# jacarerele.net
KiCad netlist of a schematic drawn in EAGLE
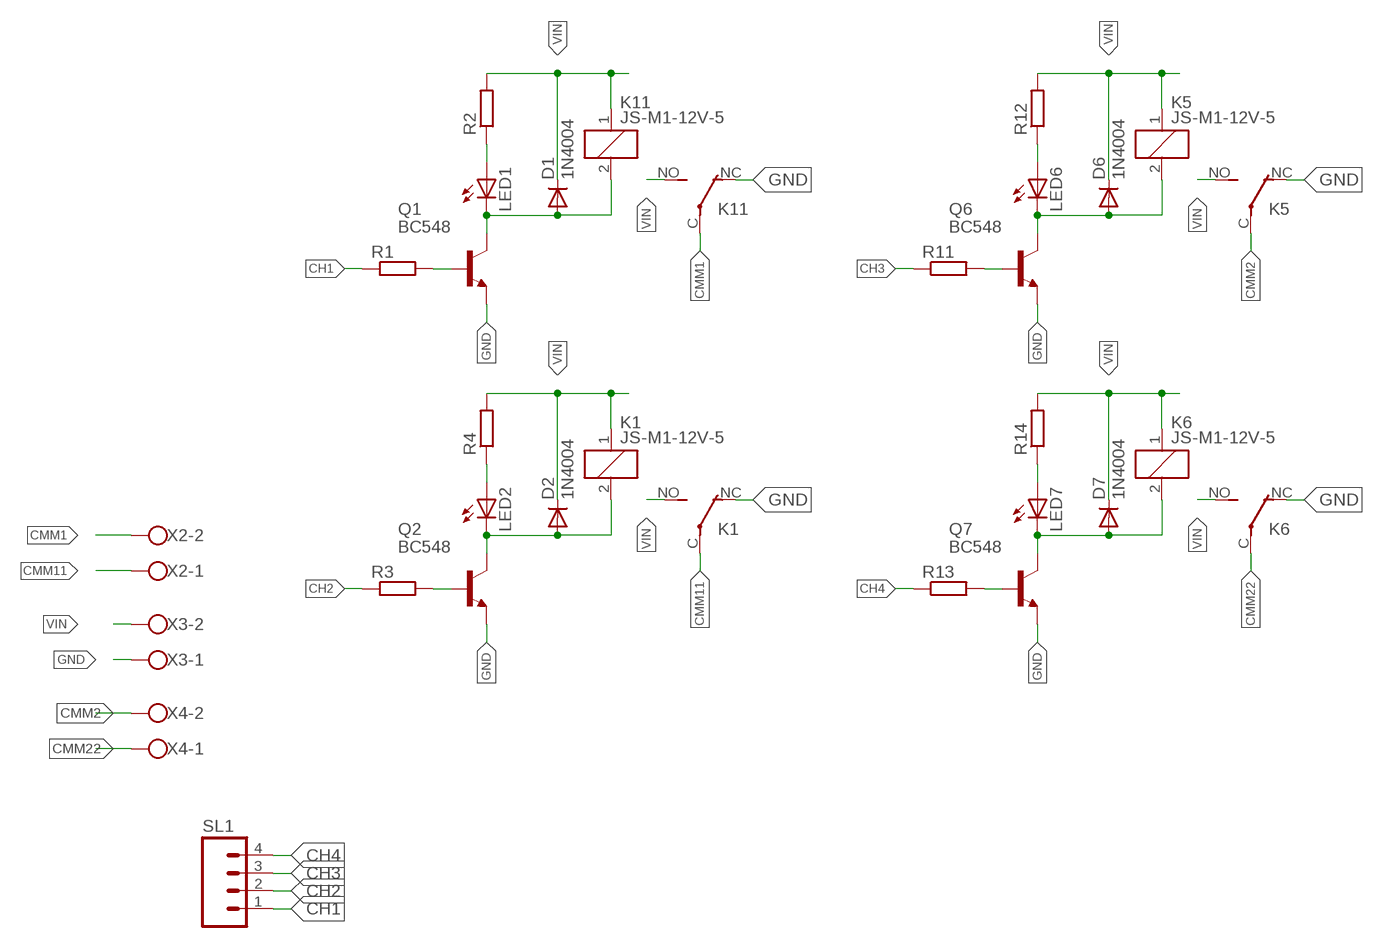
[diagram p0: schematic, sheet 1]

(export (version "E")
  (design (tool "Eeschema 10.0.6"))
  (components
    (comp (ref "D1")
      (value "1N4004")
      (footprint "eagle-import:DO41-10")
      (libsource (lib "eagle-import") (part "1N4004"))
    )
    (comp (ref "D2")
      (value "1N4004")
      (footprint "eagle-import:DO41-10")
      (libsource (lib "eagle-import") (part "1N4004"))
    )
    (comp (ref "D6")
      (value "1N4004")
      (footprint "eagle-import:DO41-10")
      (libsource (lib "eagle-import") (part "1N4004"))
    )
    (comp (ref "D7")
      (value "1N4004")
      (footprint "eagle-import:DO41-10")
      (libsource (lib "eagle-import") (part "1N4004"))
    )
    (comp (ref "K1")
      (value "JS-M1-12V-5")
      (footprint "eagle-import:JS-M")
      (fields (field (name "MF") "FARNELL") (field (name "MPN") "JSM1-12V-5"))
      (libsource (lib "eagle-import") (part "JS-M1-12V-5"))
    )
    (comp (ref "K5")
      (value "JS-M1-12V-5")
      (footprint "eagle-import:JS-M")
      (fields (field (name "MF") "FARNELL") (field (name "MPN") "JSM1-12V-5"))
      (libsource (lib "eagle-import") (part "JS-M1-12V-5"))
    )
    (comp (ref "K6")
      (value "JS-M1-12V-5")
      (footprint "eagle-import:JS-M")
      (fields (field (name "MF") "FARNELL") (field (name "MPN") "JSM1-12V-5"))
      (libsource (lib "eagle-import") (part "JS-M1-12V-5"))
    )
    (comp (ref "K11")
      (value "JS-M1-12V-5")
      (footprint "eagle-import:JS-M")
      (fields (field (name "MF") "FARNELL") (field (name "MPN") "JSM1-12V-5"))
      (libsource (lib "eagle-import") (part "JS-M1-12V-5"))
    )
    (comp (ref "LED1")
      (value "LED5MM")
      (footprint "eagle-import:LED5MM")
      (libsource (lib "eagle-import") (part "LED5MM"))
    )
    (comp (ref "LED2")
      (value "LED5MM")
      (footprint "eagle-import:LED5MM")
      (libsource (lib "eagle-import") (part "LED5MM"))
    )
    (comp (ref "LED6")
      (value "LED5MM")
      (footprint "eagle-import:LED5MM")
      (libsource (lib "eagle-import") (part "LED5MM"))
    )
    (comp (ref "LED7")
      (value "LED5MM")
      (footprint "eagle-import:LED5MM")
      (libsource (lib "eagle-import") (part "LED5MM"))
    )
    (comp (ref "Q1")
      (value "BC548")
      (footprint "eagle-import:TO92-EBC")
      (libsource (lib "eagle-import") (part "BC548"))
    )
    (comp (ref "Q2")
      (value "BC548")
      (footprint "eagle-import:TO92-EBC")
      (libsource (lib "eagle-import") (part "BC548"))
    )
    (comp (ref "Q6")
      (value "BC548")
      (footprint "eagle-import:TO92-EBC")
      (libsource (lib "eagle-import") (part "BC548"))
    )
    (comp (ref "Q7")
      (value "BC548")
      (footprint "eagle-import:TO92-EBC")
      (libsource (lib "eagle-import") (part "BC548"))
    )
    (comp (ref "R1")
      (value "R-EU_0207/10")
      (footprint "eagle-import:0207_10")
      (libsource (lib "eagle-import") (part "R-EU_0207/10"))
    )
    (comp (ref "R2")
      (value "R-EU_0207/10")
      (footprint "eagle-import:0207_10")
      (libsource (lib "eagle-import") (part "R-EU_0207/10"))
    )
    (comp (ref "R3")
      (value "R-EU_0207/10")
      (footprint "eagle-import:0207_10")
      (libsource (lib "eagle-import") (part "R-EU_0207/10"))
    )
    (comp (ref "R4")
      (value "R-EU_0207/10")
      (footprint "eagle-import:0207_10")
      (libsource (lib "eagle-import") (part "R-EU_0207/10"))
    )
    (comp (ref "R11")
      (value "R-EU_0207/10")
      (footprint "eagle-import:0207_10")
      (libsource (lib "eagle-import") (part "R-EU_0207/10"))
    )
    (comp (ref "R12")
      (value "R-EU_0207/10")
      (footprint "eagle-import:0207_10")
      (libsource (lib "eagle-import") (part "R-EU_0207/10"))
    )
    (comp (ref "R13")
      (value "R-EU_0207/10")
      (footprint "eagle-import:0207_10")
      (libsource (lib "eagle-import") (part "R-EU_0207/10"))
    )
    (comp (ref "R14")
      (value "R-EU_0207/10")
      (footprint "eagle-import:0207_10")
      (libsource (lib "eagle-import") (part "R-EU_0207/10"))
    )
    (comp (ref "SL1")
      (value "MA04")
      (footprint "eagle-import:04PA")
      (libsource (lib "eagle-import") (part "MA04"))
    )
    (comp (ref "X2")
      (value "W237-102")
      (footprint "eagle-import:W237-102")
      (fields (field (name "MPN") "237-102"))
      (libsource (lib "eagle-import") (part "W237-102"))
    )
    (comp (ref "X3")
      (value "W237-102")
      (footprint "eagle-import:W237-102")
      (fields (field (name "MPN") "237-102"))
      (libsource (lib "eagle-import") (part "W237-102"))
    )
    (comp (ref "X4")
      (value "W237-102")
      (footprint "eagle-import:W237-102")
      (fields (field (name "MPN") "237-102"))
      (libsource (lib "eagle-import") (part "W237-102"))
    )
  )
  (nets
    (net (code "1") (name "CH1") (class "Default")
      (node (ref "R1") (pin "1") (pinfunction "1_1") (pintype "passive"))
      (node (ref "SL1") (pin "1") (pinfunction "1_1") (pintype "passive"))
    )
    (net (code "2") (name "CH2") (class "Default")
      (node (ref "R3") (pin "1") (pinfunction "1_1") (pintype "passive"))
      (node (ref "SL1") (pin "2") (pinfunction "2_2") (pintype "passive"))
    )
    (net (code "3") (name "CH3") (class "Default")
      (node (ref "R11") (pin "1") (pinfunction "1_1") (pintype "passive"))
      (node (ref "SL1") (pin "3") (pinfunction "3_3") (pintype "passive"))
    )
    (net (code "4") (name "CH4") (class "Default")
      (node (ref "R13") (pin "1") (pinfunction "1_1") (pintype "passive"))
      (node (ref "SL1") (pin "4") (pinfunction "4_4") (pintype "passive"))
    )
    (net (code "5") (name "CMM1") (class "Default")
      (node (ref "K11") (pin "C") (pinfunction "P_C") (pintype "passive"))
      (node (ref "X2") (pin "2") (pinfunction "KL_2") (pintype "passive"))
    )
    (net (code "6") (name "CMM2") (class "Default")
      (node (ref "K5") (pin "C") (pinfunction "P_C") (pintype "passive"))
      (node (ref "X4") (pin "2") (pinfunction "KL_2") (pintype "passive"))
    )
    (net (code "7") (name "CMM11") (class "Default")
      (node (ref "K1") (pin "C") (pinfunction "P_C") (pintype "passive"))
      (node (ref "X2") (pin "1") (pinfunction "KL_1") (pintype "passive"))
    )
    (net (code "8") (name "CMM22") (class "Default")
      (node (ref "K6") (pin "C") (pinfunction "P_C") (pintype "passive"))
      (node (ref "X4") (pin "1") (pinfunction "KL_1") (pintype "passive"))
    )
    (net (code "9") (name "GND") (class "Default")
      (node (ref "K1") (pin "NC") (pinfunction "O_NC") (pintype "passive"))
      (node (ref "K11") (pin "NC") (pinfunction "O_NC") (pintype "passive"))
      (node (ref "K5") (pin "NC") (pinfunction "O_NC") (pintype "passive"))
      (node (ref "K6") (pin "NC") (pinfunction "O_NC") (pintype "passive"))
      (node (ref "Q1") (pin "E") (pinfunction "E_E") (pintype "passive"))
      (node (ref "Q2") (pin "E") (pinfunction "E_E") (pintype "passive"))
      (node (ref "Q6") (pin "E") (pinfunction "E_E") (pintype "passive"))
      (node (ref "Q7") (pin "E") (pinfunction "E_E") (pintype "passive"))
      (node (ref "X3") (pin "1") (pinfunction "KL_1") (pintype "passive"))
    )
    (net (code "10") (name "Net-(LED1-C)") (class "Default")
      (node (ref "D1") (pin "A") (pinfunction "A_A") (pintype "passive"))
      (node (ref "K11") (pin "2") (pinfunction "2_2") (pintype "passive"))
      (node (ref "LED1") (pin "K") (pinfunction "C_K") (pintype "passive"))
      (node (ref "Q1") (pin "C") (pinfunction "C_C") (pintype "passive"))
    )
    (net (code "11") (name "Net-(LED1-PadA)") (class "Default")
      (node (ref "LED1") (pin "A") (pinfunction "A_A") (pintype "passive"))
      (node (ref "R2") (pin "1") (pinfunction "1_1") (pintype "passive"))
    )
    (net (code "12") (name "Net-(LED2-C)") (class "Default")
      (node (ref "D2") (pin "A") (pinfunction "A_A") (pintype "passive"))
      (node (ref "K1") (pin "2") (pinfunction "2_2") (pintype "passive"))
      (node (ref "LED2") (pin "K") (pinfunction "C_K") (pintype "passive"))
      (node (ref "Q2") (pin "C") (pinfunction "C_C") (pintype "passive"))
    )
    (net (code "13") (name "Net-(LED2-PadA)") (class "Default")
      (node (ref "LED2") (pin "A") (pinfunction "A_A") (pintype "passive"))
      (node (ref "R4") (pin "1") (pinfunction "1_1") (pintype "passive"))
    )
    (net (code "14") (name "Net-(LED6-C)") (class "Default")
      (node (ref "D6") (pin "A") (pinfunction "A_A") (pintype "passive"))
      (node (ref "K5") (pin "2") (pinfunction "2_2") (pintype "passive"))
      (node (ref "LED6") (pin "K") (pinfunction "C_K") (pintype "passive"))
      (node (ref "Q6") (pin "C") (pinfunction "C_C") (pintype "passive"))
    )
    (net (code "15") (name "Net-(LED6-PadA)") (class "Default")
      (node (ref "LED6") (pin "A") (pinfunction "A_A") (pintype "passive"))
      (node (ref "R12") (pin "1") (pinfunction "1_1") (pintype "passive"))
    )
    (net (code "16") (name "Net-(LED7-C)") (class "Default")
      (node (ref "D7") (pin "A") (pinfunction "A_A") (pintype "passive"))
      (node (ref "K6") (pin "2") (pinfunction "2_2") (pintype "passive"))
      (node (ref "LED7") (pin "K") (pinfunction "C_K") (pintype "passive"))
      (node (ref "Q7") (pin "C") (pinfunction "C_C") (pintype "passive"))
    )
    (net (code "17") (name "Net-(LED7-PadA)") (class "Default")
      (node (ref "LED7") (pin "A") (pinfunction "A_A") (pintype "passive"))
      (node (ref "R14") (pin "1") (pinfunction "1_1") (pintype "passive"))
    )
    (net (code "18") (name "Net-(Q1-PadB)") (class "Default")
      (node (ref "Q1") (pin "B") (pinfunction "B_B") (pintype "passive"))
      (node (ref "R1") (pin "2") (pinfunction "2_2") (pintype "passive"))
    )
    (net (code "19") (name "Net-(Q2-PadB)") (class "Default")
      (node (ref "Q2") (pin "B") (pinfunction "B_B") (pintype "passive"))
      (node (ref "R3") (pin "2") (pinfunction "2_2") (pintype "passive"))
    )
    (net (code "20") (name "Net-(Q6-PadB)") (class "Default")
      (node (ref "Q6") (pin "B") (pinfunction "B_B") (pintype "passive"))
      (node (ref "R11") (pin "2") (pinfunction "2_2") (pintype "passive"))
    )
    (net (code "21") (name "Net-(Q7-PadB)") (class "Default")
      (node (ref "Q7") (pin "B") (pinfunction "B_B") (pintype "passive"))
      (node (ref "R13") (pin "2") (pinfunction "2_2") (pintype "passive"))
    )
    (net (code "22") (name "VIN") (class "Default")
      (node (ref "D1") (pin "C") (pinfunction "C_C") (pintype "passive"))
      (node (ref "D2") (pin "C") (pinfunction "C_C") (pintype "passive"))
      (node (ref "D6") (pin "C") (pinfunction "C_C") (pintype "passive"))
      (node (ref "D7") (pin "C") (pinfunction "C_C") (pintype "passive"))
      (node (ref "K1") (pin "1") (pinfunction "1_1") (pintype "passive"))
      (node (ref "K1") (pin "NO") (pinfunction "S_NO") (pintype "passive"))
      (node (ref "K11") (pin "1") (pinfunction "1_1") (pintype "passive"))
      (node (ref "K11") (pin "NO") (pinfunction "S_NO") (pintype "passive"))
      (node (ref "K5") (pin "1") (pinfunction "1_1") (pintype "passive"))
      (node (ref "K5") (pin "NO") (pinfunction "S_NO") (pintype "passive"))
      (node (ref "K6") (pin "1") (pinfunction "1_1") (pintype "passive"))
      (node (ref "K6") (pin "NO") (pinfunction "S_NO") (pintype "passive"))
      (node (ref "R12") (pin "2") (pinfunction "2_2") (pintype "passive"))
      (node (ref "R14") (pin "2") (pinfunction "2_2") (pintype "passive"))
      (node (ref "R2") (pin "2") (pinfunction "2_2") (pintype "passive"))
      (node (ref "R4") (pin "2") (pinfunction "2_2") (pintype "passive"))
      (node (ref "X3") (pin "2") (pinfunction "KL_2") (pintype "passive"))
    )
  )
)
